# ESP32-S3-WROOM-1-BREAKOUT.net
KiCad netlist of a schematic drawn in Altium Designer
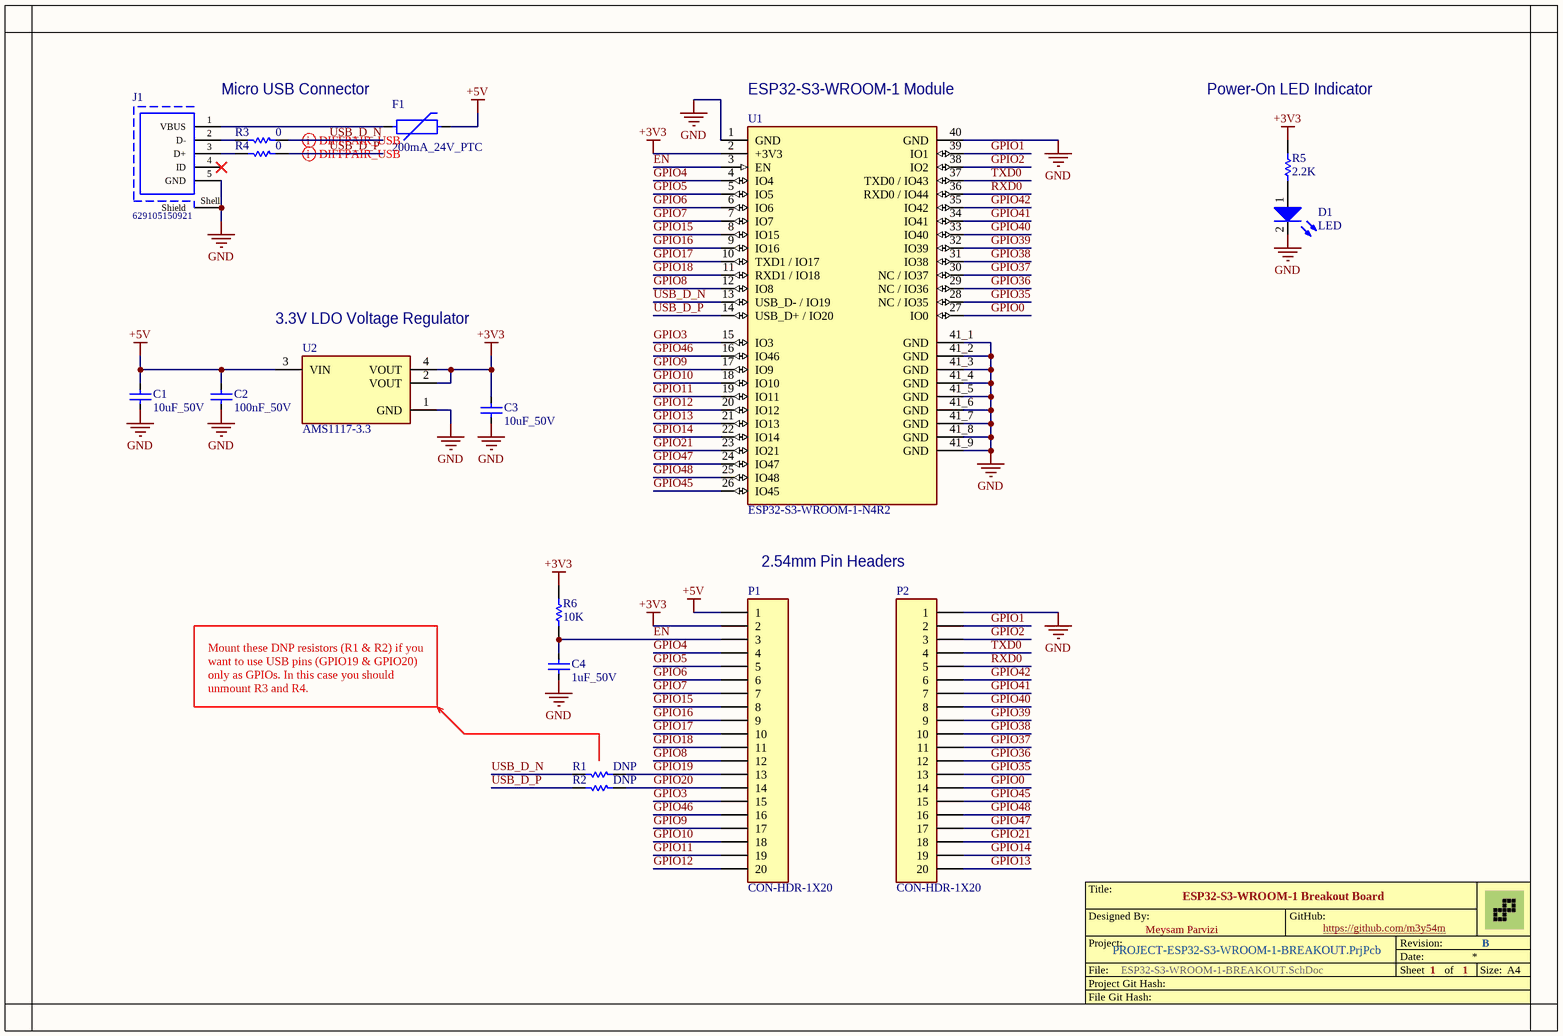
[diagram p0: ESP32-S3-WROOM-1-BREAKOUT.SchDoc]

(export (version "E")
  (design (tool "Eeschema 10.0.6"))
  (components
    (comp (ref "C1")
      (value "10uF_50V")
      (footprint "CustomLib-Package:C0805")
      (description "C0805 0.10 μF X7R 30ppm/°C 10.00% 50 V")
      (fields
        (field (name "MANUFACTURER") "KEMET")
        (field (name "MANUFACTURER PART NUMBER") "C0805C104K5RAC7411")
      )
      (libsource (lib "CustomLib-Package") (part "CAPACITOR"))
    )
    (comp (ref "C2")
      (value "100nF_50V")
      (footprint "CustomLib-Package:C0805")
      (description "C0805 0.10 μF X7R 30ppm/°C 10.00% 50 V")
      (fields
        (field (name "MANUFACTURER") "KEMET")
        (field (name "MANUFACTURER PART NUMBER") "C0805C104K5RAC7411")
      )
      (libsource (lib "CustomLib-Package") (part "CAPACITOR"))
    )
    (comp (ref "C3")
      (value "10uF_50V")
      (footprint "CustomLib-Package:C0805")
      (description "C0805 0.10 μF X7R 30ppm/°C 10.00% 50 V")
      (fields
        (field (name "MANUFACTURER") "KEMET")
        (field (name "MANUFACTURER PART NUMBER") "C0805C104K5RAC7411")
      )
      (libsource (lib "CustomLib-Package") (part "CAPACITOR"))
    )
    (comp (ref "C4")
      (value "1uF_50V")
      (footprint "CustomLib-Package:C0805")
      (description "C0805 0.10 μF X7R 30ppm/°C 10.00% 50 V")
      (fields
        (field (name "MANUFACTURER") "KEMET")
        (field (name "MANUFACTURER PART NUMBER") "C0805C104K5RAC7411")
      )
      (libsource (lib "CustomLib-Package") (part "CAPACITOR"))
    )
    (comp (ref "D1")
      (value "LED")
      (footprint "LED0805")
      (description "Typical LED")
      (libsource (lib "CustomLib-Package") (part "LED"))
    )
    (comp (ref "F1")
      (value "200mA_24V_PTC")
      (footprint "CustomLib-Package:R1206")
      (description "FUSE PPTC 200MA (1206) 24V RESETTABLE")
      (fields (field (name "Comment") "NANOSMDC020F-2"))
      (libsource (lib "CustomLib-Package") (part "FUSE-PTC"))
    )
    (comp (ref "J1")
      (value "629105150921")
      (footprint "CON-MICRO-USB-B-SMD-WITH-HOLDER")
      (description "Micro USB 2.0 Type AB Receptacle WR-COM, Horizontal, SMT")
      (fields (field (name "MANUFACTURER") "Wurth Elektronik") (field (name "PUBLISHER") "WurthElektronik"))
      (libsource (lib "CustomLib-Package") (part "CON-MICRO-USB-AB-RCPT-SMD"))
    )
    (comp (ref "P1")
      (value "CON-HDR-1X20")
      (footprint "CON-HDR-1X20-2.54")
      (description "Pin Header, 20-Pin")
      (fields (field (name "PUBLISHER") "Altium Limited"))
      (libsource (lib "CustomLib-Package") (part "CON-HDR-1X20"))
    )
    (comp (ref "P2")
      (value "CON-HDR-1X20")
      (footprint "CON-HDR-1X20-2.54")
      (description "Pin Header, 20-Pin")
      (fields (field (name "PUBLISHER") "Altium Limited"))
      (libsource (lib "") (part "CON-HDR-1X20_1"))
    )
    (comp (ref "R1")
      (value "DNP")
      (footprint "R0603")
      (description "RES SMD 10K OHM 1% 1/8W 0805")
      (fields (field (name "TOLERANCE") "1%") (field (name "Comment") "CRG0805F10K"))
      (libsource (lib "CustomLib-Package") (part "RESISTOR"))
    )
    (comp (ref "R2")
      (value "DNP")
      (footprint "R0603")
      (description "RES SMD 10K OHM 1% 1/8W 0805")
      (fields (field (name "TOLERANCE") "1%") (field (name "Comment") "CRG0805F10K"))
      (libsource (lib "CustomLib-Package") (part "RESISTOR"))
    )
    (comp (ref "R3")
      (value "0")
      (footprint "R0603")
      (description "RES SMD 10K OHM 1% 1/8W 0805")
      (fields (field (name "TOLERANCE") "1%") (field (name "Comment") "CRG0805F10K"))
      (libsource (lib "CustomLib-Package") (part "RESISTOR"))
    )
    (comp (ref "R4")
      (value "0")
      (footprint "R0603")
      (description "RES SMD 10K OHM 1% 1/8W 0805")
      (fields (field (name "TOLERANCE") "1%") (field (name "Comment") "CRG0805F10K"))
      (libsource (lib "CustomLib-Package") (part "RESISTOR"))
    )
    (comp (ref "R5")
      (value "2.2K")
      (footprint "CustomLib-Package:R0805")
      (description "RES SMD 10K OHM 1% 1/8W 0805")
      (fields (field (name "TOLERANCE") "1%") (field (name "Comment") "CRG0805F10K"))
      (libsource (lib "CustomLib-Package") (part "RESISTOR"))
    )
    (comp (ref "R6")
      (value "10K")
      (footprint "CustomLib-Package:R0805")
      (description "RES SMD 10K OHM 1% 1/8W 0805")
      (fields (field (name "TOLERANCE") "1%") (field (name "Comment") "CRG0805F10K"))
      (libsource (lib "CustomLib-Package") (part "RESISTOR"))
    )
    (comp (ref "U1")
      (value "ESP32-S3-WROOM-1-N4R2")
      (footprint "ESP32-S3-WROOM-1_NO-KEEPOUT")
      (fields
        (field (name "MPN") "ESP32-S3-WROOM-1-N16R2")
        (field (name "MF") "Espressif Systems")
        (field (name "DIGI-KEY_PART_NUMBER") "1965-ESP32-S3-WROOM-1-N16R2TR-ND")
      )
      (libsource (lib "CustomLib-Package") (part "ESP32-S3-WROOM-1"))
    )
    (comp (ref "U2")
      (value "AMS1117-3.3")
      (footprint "CustomLib-Package:SOT-223")
      (description "IC REG LINEAR 3.3V 800MA SOT223")
      (libsource (lib "CustomLib-Package") (part "LD1117"))
    )
  )
  (nets
    (net (code "1") (name "+3V3") (class "Default")
      (node (ref "C3") (pin "1") (pinfunction "1_1") (pintype "passive"))
      (node (ref "P1") (pin "2") (pinfunction "2_2") (pintype "passive"))
      (node (ref "R5") (pin "1") (pinfunction "1_1") (pintype "passive"))
      (node (ref "R6") (pin "2") (pinfunction "2_2") (pintype "passive"))
      (node (ref "U1") (pin "2") (pinfunction "+3V3_2") (pintype "power_in"))
      (node (ref "U2") (pin "2") (pinfunction "VOUT_2") (pintype "power_in"))
      (node (ref "U2") (pin "4") (pinfunction "VOUT_4") (pintype "power_in"))
    )
    (net (code "2") (name "+5V") (class "Default")
      (node (ref "C1") (pin "1") (pinfunction "1_1") (pintype "passive"))
      (node (ref "C2") (pin "1") (pinfunction "1_1") (pintype "passive"))
      (node (ref "F1") (pin "2") (pinfunction "2_2") (pintype "passive"))
      (node (ref "P1") (pin "1") (pinfunction "1_1") (pintype "passive"))
      (node (ref "U2") (pin "3") (pinfunction "VIN_3") (pintype "power_in"))
    )
    (net (code "3") (name "/EN") (class "Default")
      (node (ref "C4") (pin "1") (pinfunction "1_1") (pintype "passive"))
      (node (ref "P1") (pin "3") (pinfunction "3_3") (pintype "passive"))
      (node (ref "R6") (pin "1") (pinfunction "1_1") (pintype "passive"))
      (node (ref "U1") (pin "3") (pinfunction "EN_3") (pintype "input"))
    )
    (net (code "4") (name "/GPIO0") (class "Default")
      (node (ref "P2") (pin "14") (pinfunction "14_14") (pintype "passive"))
      (node (ref "U1") (pin "27") (pinfunction "IO0_27") (pintype "bidirectional"))
    )
    (net (code "5") (name "/GPIO1") (class "Default")
      (node (ref "P2") (pin "2") (pinfunction "2_2") (pintype "passive"))
      (node (ref "U1") (pin "39") (pinfunction "IO1_39") (pintype "bidirectional"))
    )
    (net (code "6") (name "/GPIO2") (class "Default")
      (node (ref "P2") (pin "3") (pinfunction "3_3") (pintype "passive"))
      (node (ref "U1") (pin "38") (pinfunction "IO2_38") (pintype "bidirectional"))
    )
    (net (code "7") (name "/GPIO3") (class "Default")
      (node (ref "P1") (pin "15") (pinfunction "15_15") (pintype "passive"))
      (node (ref "U1") (pin "15") (pinfunction "IO3_15") (pintype "bidirectional"))
    )
    (net (code "8") (name "/GPIO4") (class "Default")
      (node (ref "P1") (pin "4") (pinfunction "4_4") (pintype "passive"))
      (node (ref "U1") (pin "4") (pinfunction "IO4_4") (pintype "bidirectional"))
    )
    (net (code "9") (name "/GPIO5") (class "Default")
      (node (ref "P1") (pin "5") (pinfunction "5_5") (pintype "passive"))
      (node (ref "U1") (pin "5") (pinfunction "IO5_5") (pintype "bidirectional"))
    )
    (net (code "10") (name "/GPIO6") (class "Default")
      (node (ref "P1") (pin "6") (pinfunction "6_6") (pintype "passive"))
      (node (ref "U1") (pin "6") (pinfunction "IO6_6") (pintype "bidirectional"))
    )
    (net (code "11") (name "/GPIO7") (class "Default")
      (node (ref "P1") (pin "7") (pinfunction "7_7") (pintype "passive"))
      (node (ref "U1") (pin "7") (pinfunction "IO7_7") (pintype "bidirectional"))
    )
    (net (code "12") (name "/GPIO8") (class "Default")
      (node (ref "P1") (pin "12") (pinfunction "12_12") (pintype "passive"))
      (node (ref "U1") (pin "12") (pinfunction "IO8_12") (pintype "bidirectional"))
    )
    (net (code "13") (name "/GPIO9") (class "Default")
      (node (ref "P1") (pin "17") (pinfunction "17_17") (pintype "passive"))
      (node (ref "U1") (pin "17") (pinfunction "IO9_17") (pintype "bidirectional"))
    )
    (net (code "14") (name "/GPIO10") (class "Default")
      (node (ref "P1") (pin "18") (pinfunction "18_18") (pintype "passive"))
      (node (ref "U1") (pin "18") (pinfunction "IO10_18") (pintype "bidirectional"))
    )
    (net (code "15") (name "/GPIO11") (class "Default")
      (node (ref "P1") (pin "19") (pinfunction "19_19") (pintype "passive"))
      (node (ref "U1") (pin "19") (pinfunction "IO11_19") (pintype "bidirectional"))
    )
    (net (code "16") (name "/GPIO12") (class "Default")
      (node (ref "P1") (pin "20") (pinfunction "20_20") (pintype "passive"))
      (node (ref "U1") (pin "20") (pinfunction "IO12_20") (pintype "bidirectional"))
    )
    (net (code "17") (name "/GPIO13") (class "Default")
      (node (ref "P2") (pin "20") (pinfunction "20_20") (pintype "passive"))
      (node (ref "U1") (pin "21") (pinfunction "IO13_21") (pintype "bidirectional"))
    )
    (net (code "18") (name "/GPIO14") (class "Default")
      (node (ref "P2") (pin "19") (pinfunction "19_19") (pintype "passive"))
      (node (ref "U1") (pin "22") (pinfunction "IO14_22") (pintype "bidirectional"))
    )
    (net (code "19") (name "/GPIO15") (class "Default")
      (node (ref "P1") (pin "8") (pinfunction "8_8") (pintype "passive"))
      (node (ref "U1") (pin "8") (pinfunction "IO15_8") (pintype "bidirectional"))
    )
    (net (code "20") (name "/GPIO16") (class "Default")
      (node (ref "P1") (pin "9") (pinfunction "9_9") (pintype "passive"))
      (node (ref "U1") (pin "9") (pinfunction "IO16_9") (pintype "bidirectional"))
    )
    (net (code "21") (name "/GPIO17") (class "Default")
      (node (ref "P1") (pin "10") (pinfunction "10_10") (pintype "passive"))
      (node (ref "U1") (pin "10") (pinfunction "TXD1_/_IO17_10") (pintype "bidirectional"))
    )
    (net (code "22") (name "/GPIO18") (class "Default")
      (node (ref "P1") (pin "11") (pinfunction "11_11") (pintype "passive"))
      (node (ref "U1") (pin "11") (pinfunction "RXD1_/_IO18_11") (pintype "bidirectional"))
    )
    (net (code "23") (name "/GPIO19") (class "Default")
      (node (ref "P1") (pin "13") (pinfunction "13_13") (pintype "passive"))
      (node (ref "R1") (pin "1") (pinfunction "1_1") (pintype "passive"))
    )
    (net (code "24") (name "/GPIO20") (class "Default")
      (node (ref "P1") (pin "14") (pinfunction "14_14") (pintype "passive"))
      (node (ref "R2") (pin "1") (pinfunction "1_1") (pintype "passive"))
    )
    (net (code "25") (name "/GPIO21") (class "Default")
      (node (ref "P2") (pin "18") (pinfunction "18_18") (pintype "passive"))
      (node (ref "U1") (pin "23") (pinfunction "IO21_23") (pintype "bidirectional"))
    )
    (net (code "26") (name "/GPIO35") (class "Default")
      (node (ref "P2") (pin "13") (pinfunction "13_13") (pintype "passive"))
      (node (ref "U1") (pin "28") (pinfunction "NC_/_IO35_28") (pintype "bidirectional"))
    )
    (net (code "27") (name "/GPIO36") (class "Default")
      (node (ref "P2") (pin "12") (pinfunction "12_12") (pintype "passive"))
      (node (ref "U1") (pin "29") (pinfunction "NC_/_IO36_29") (pintype "bidirectional"))
    )
    (net (code "28") (name "/GPIO37") (class "Default")
      (node (ref "P2") (pin "11") (pinfunction "11_11") (pintype "passive"))
      (node (ref "U1") (pin "30") (pinfunction "NC_/_IO37_30") (pintype "bidirectional"))
    )
    (net (code "29") (name "/GPIO38") (class "Default")
      (node (ref "P2") (pin "10") (pinfunction "10_10") (pintype "passive"))
      (node (ref "U1") (pin "31") (pinfunction "IO38_31") (pintype "bidirectional"))
    )
    (net (code "30") (name "/GPIO39") (class "Default")
      (node (ref "P2") (pin "9") (pinfunction "9_9") (pintype "passive"))
      (node (ref "U1") (pin "32") (pinfunction "IO39_32") (pintype "bidirectional"))
    )
    (net (code "31") (name "/GPIO40") (class "Default")
      (node (ref "P2") (pin "8") (pinfunction "8_8") (pintype "passive"))
      (node (ref "U1") (pin "33") (pinfunction "IO40_33") (pintype "bidirectional"))
    )
    (net (code "32") (name "/GPIO41") (class "Default")
      (node (ref "P2") (pin "7") (pinfunction "7_7") (pintype "passive"))
      (node (ref "U1") (pin "34") (pinfunction "IO41_34") (pintype "bidirectional"))
    )
    (net (code "33") (name "/GPIO42") (class "Default")
      (node (ref "P2") (pin "6") (pinfunction "6_6") (pintype "passive"))
      (node (ref "U1") (pin "35") (pinfunction "IO42_35") (pintype "bidirectional"))
    )
    (net (code "34") (name "/GPIO45") (class "Default")
      (node (ref "P2") (pin "15") (pinfunction "15_15") (pintype "passive"))
      (node (ref "U1") (pin "26") (pinfunction "IO45_26") (pintype "bidirectional"))
    )
    (net (code "35") (name "/GPIO46") (class "Default")
      (node (ref "P1") (pin "16") (pinfunction "16_16") (pintype "passive"))
      (node (ref "U1") (pin "16") (pinfunction "IO46_16") (pintype "bidirectional"))
    )
    (net (code "36") (name "/GPIO47") (class "Default")
      (node (ref "P2") (pin "17") (pinfunction "17_17") (pintype "passive"))
      (node (ref "U1") (pin "24") (pinfunction "IO47_24") (pintype "bidirectional"))
    )
    (net (code "37") (name "/GPIO48") (class "Default")
      (node (ref "P2") (pin "16") (pinfunction "16_16") (pintype "passive"))
      (node (ref "U1") (pin "25") (pinfunction "IO48_25") (pintype "bidirectional"))
    )
    (net (code "38") (name "/RXD0") (class "Default")
      (node (ref "P2") (pin "5") (pinfunction "5_5") (pintype "passive"))
      (node (ref "U1") (pin "36") (pinfunction "RXD0_/_IO44_36") (pintype "bidirectional"))
    )
    (net (code "39") (name "/TXD0") (class "Default")
      (node (ref "P2") (pin "4") (pinfunction "4_4") (pintype "passive"))
      (node (ref "U1") (pin "37") (pinfunction "TXD0_/_IO43_37") (pintype "bidirectional"))
    )
    (net (code "40") (name "/USB_D_N") (class "Default")
      (node (ref "R1") (pin "2") (pinfunction "2_2") (pintype "passive"))
      (node (ref "R3") (pin "1") (pinfunction "1_1") (pintype "passive"))
      (node (ref "U1") (pin "13") (pinfunction "USB_D-_/_IO19_13") (pintype "bidirectional"))
    )
    (net (code "41") (name "/USB_D_P") (class "Default")
      (node (ref "R2") (pin "2") (pinfunction "2_2") (pintype "passive"))
      (node (ref "R4") (pin "1") (pinfunction "1_1") (pintype "passive"))
      (node (ref "U1") (pin "14") (pinfunction "USB_D+_/_IO20_14") (pintype "bidirectional"))
    )
    (net (code "42") (name "GND") (class "Default")
      (node (ref "C1") (pin "2") (pinfunction "2_2") (pintype "passive"))
      (node (ref "C2") (pin "2") (pinfunction "2_2") (pintype "passive"))
      (node (ref "C3") (pin "2") (pinfunction "2_2") (pintype "passive"))
      (node (ref "C4") (pin "2") (pinfunction "2_2") (pintype "passive"))
      (node (ref "D1") (pin "2") (pinfunction "K_2") (pintype "passive"))
      (node (ref "J1") (pin "5") (pinfunction "GND_5") (pintype "passive"))
      (node (ref "J1") (pin "Shell") (pinfunction "Shield_Shell") (pintype "passive"))
      (node (ref "P2") (pin "1") (pinfunction "1_1") (pintype "passive"))
      (node (ref "U1") (pin "1") (pinfunction "GND_1") (pintype "power_in"))
      (node (ref "U1") (pin "40") (pinfunction "GND_40") (pintype "power_in"))
      (node (ref "U1") (pin "41_1") (pinfunction "GND_41_1") (pintype "power_in"))
      (node (ref "U1") (pin "41_2") (pinfunction "GND_41_2") (pintype "power_in"))
      (node (ref "U1") (pin "41_3") (pinfunction "GND_41_3") (pintype "power_in"))
      (node (ref "U1") (pin "41_4") (pinfunction "GND_41_4") (pintype "power_in"))
      (node (ref "U1") (pin "41_5") (pinfunction "GND_41_5") (pintype "power_in"))
      (node (ref "U1") (pin "41_6") (pinfunction "GND_41_6") (pintype "power_in"))
      (node (ref "U1") (pin "41_7") (pinfunction "GND_41_7") (pintype "power_in"))
      (node (ref "U1") (pin "41_8") (pinfunction "GND_41_8") (pintype "power_in"))
      (node (ref "U1") (pin "41_9") (pinfunction "GND_41_9") (pintype "power_in"))
      (node (ref "U2") (pin "1") (pinfunction "GND_1") (pintype "power_in"))
    )
    (net (code "43") (name "Net-(D1-A)") (class "Default")
      (node (ref "D1") (pin "1") (pinfunction "A_1") (pintype "passive"))
      (node (ref "R5") (pin "2") (pinfunction "2_2") (pintype "passive"))
    )
    (net (code "44") (name "Net-(J1-D+)") (class "Default")
      (node (ref "J1") (pin "3") (pinfunction "D+_3") (pintype "passive"))
      (node (ref "R4") (pin "2") (pinfunction "2_2") (pintype "passive"))
    )
    (net (code "45") (name "Net-(J1-D-)") (class "Default")
      (node (ref "J1") (pin "2") (pinfunction "D-_2") (pintype "passive"))
      (node (ref "R3") (pin "2") (pinfunction "2_2") (pintype "passive"))
    )
    (net (code "46") (name "Net-(J1-VBUS)") (class "Default")
      (node (ref "F1") (pin "1") (pinfunction "1_1") (pintype "passive"))
      (node (ref "J1") (pin "1") (pinfunction "VBUS_1") (pintype "passive"))
    )
    (net (code "47") (name "unconnected-(J1-ID-Pad4)") (class "Default")
      (node (ref "J1") (pin "4") (pinfunction "ID_4") (pintype "passive+no_connect"))
    )
  )
)
